# Application_-_out8_16A_-_bistable_relay_.net
KiCad netlist of a schematic drawn in EAGLE
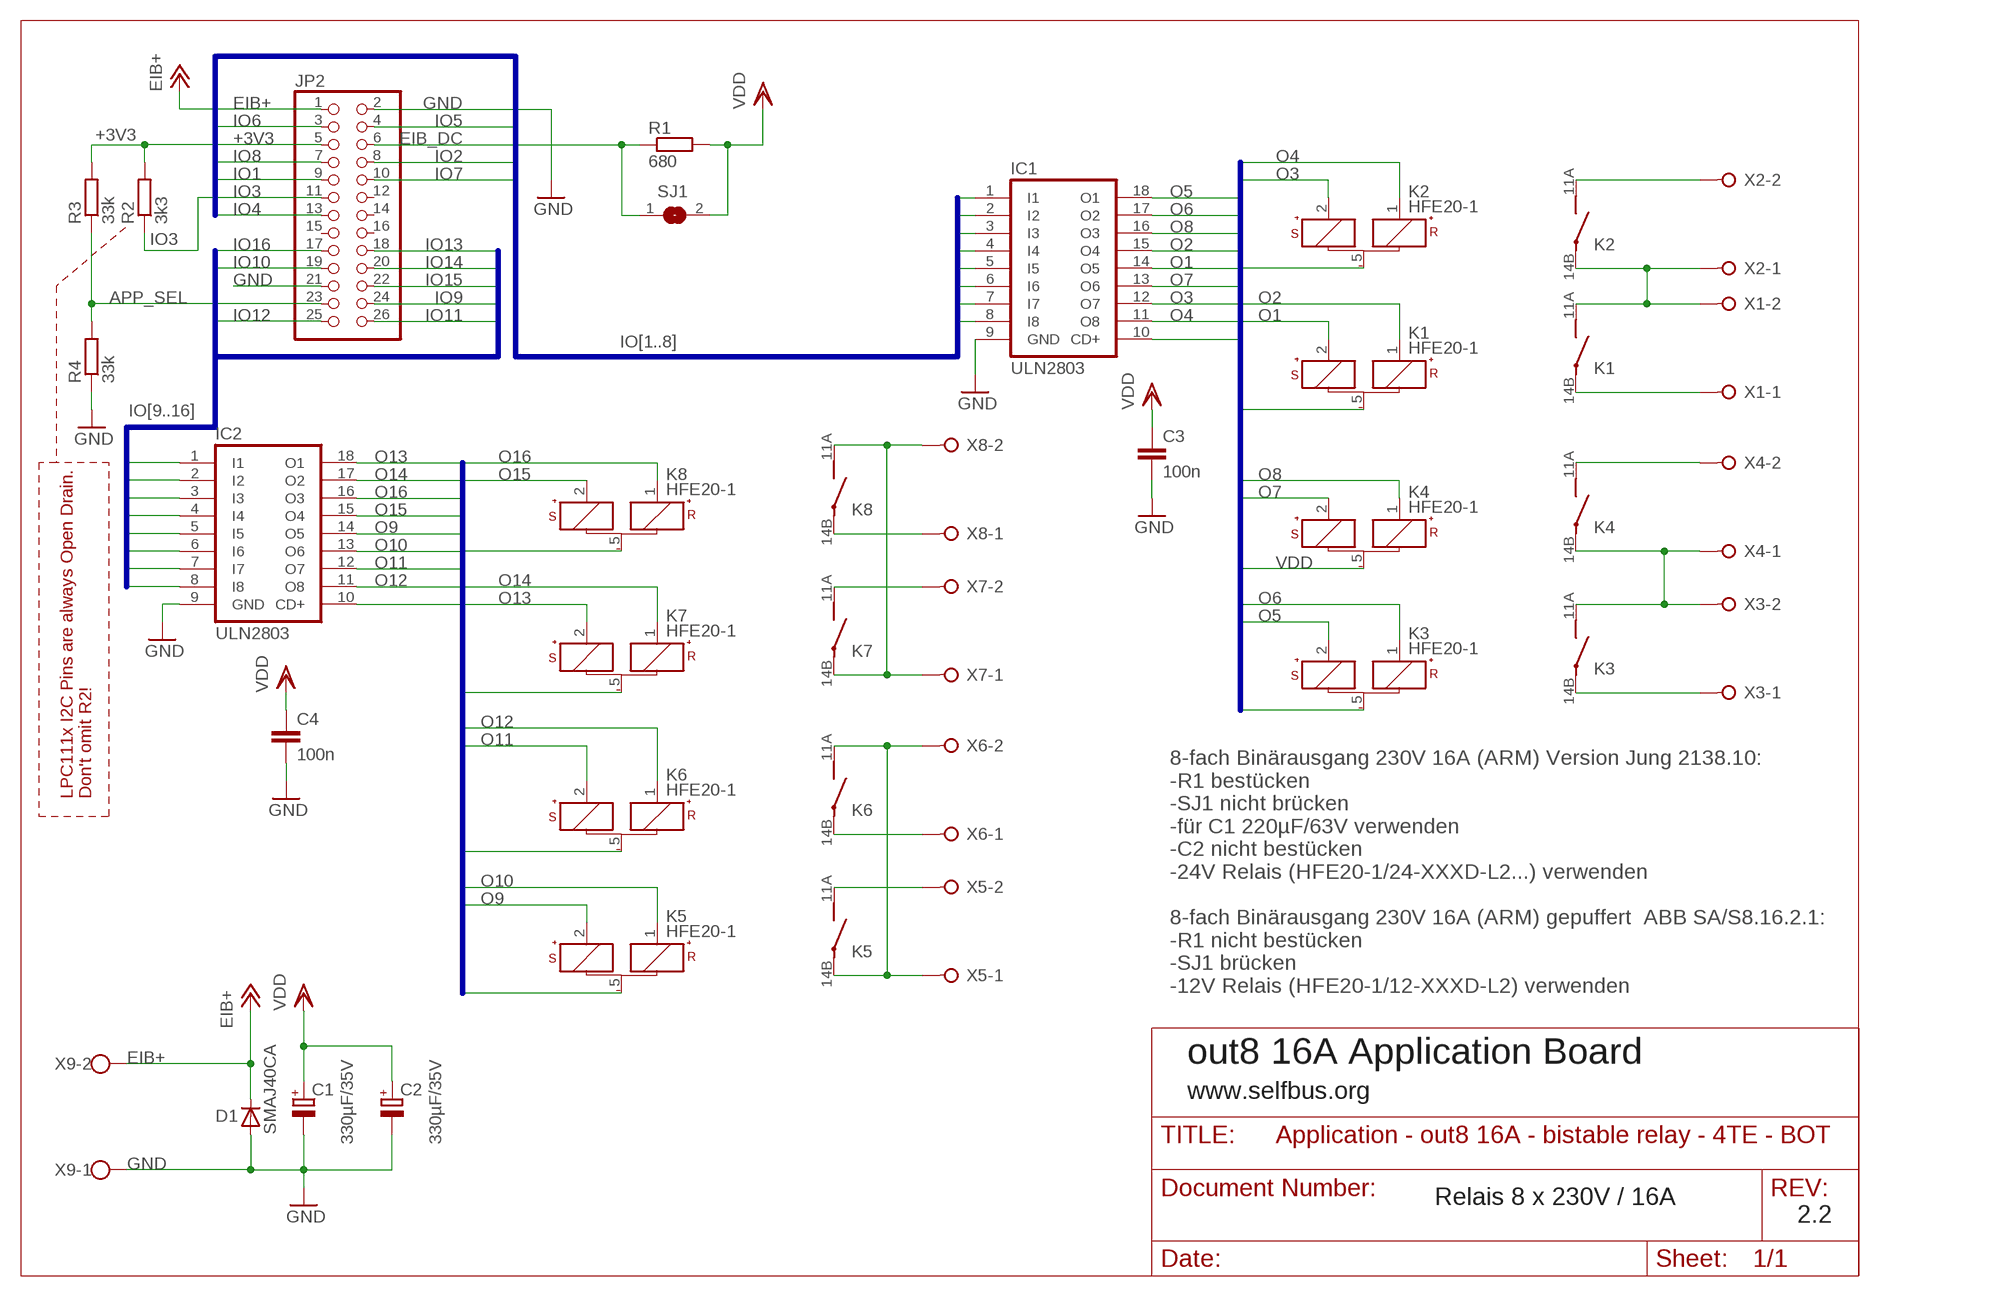
[diagram p0: schematic, sheet 1]

(export (version "E")
  (design (tool "Eeschema 10.0.6"))
  (components
    (comp (ref "C1")
      (value "330µF/35V")
      (footprint "eagle-import:E3,5-8")
      (libsource (lib "eagle-import") (part "CPOL-EUE3.5-8"))
    )
    (comp (ref "C2")
      (value "330µF/35V")
      (footprint "eagle-import:E3,5-8")
      (libsource (lib "eagle-import") (part "CPOL-EUE3.5-8"))
    )
    (comp (ref "C3")
      (value "100n")
      (footprint "eagle-import:C1206")
      (libsource (lib "eagle-import") (part "C-EUC1206"))
    )
    (comp (ref "C4")
      (value "100n")
      (footprint "eagle-import:C1206")
      (libsource (lib "eagle-import") (part "C-EUC1206"))
    )
    (comp (ref "D1")
      (value "SMAJ40CA")
      (footprint "eagle-import:SMB")
      (libsource (lib "eagle-import") (part "D-SMB"))
    )
    (comp (ref "IC1")
      (value "ULN2803")
      (footprint "eagle-import:SO18W")
      (libsource (lib "eagle-import") (part "ULN2803ASOP18"))
    )
    (comp (ref "IC2")
      (value "ULN2803")
      (footprint "eagle-import:SO18W")
      (libsource (lib "eagle-import") (part "ULN2803ASOP18"))
    )
    (comp (ref "JP2")
      (value "PINHD-2X13_2.54-SMD")
      (footprint "eagle-import:2X13SMD")
      (libsource (lib "eagle-import") (part "PINHD-2X13_2.54-SMD"))
    )
    (comp (ref "K1")
      (value "HFE20-1")
      (footprint "eagle-import:HFE20-3-504")
      (libsource (lib "eagle-import") (part "HFE20-1-024-1HD504"))
    )
    (comp (ref "K2")
      (value "HFE20-1")
      (footprint "eagle-import:HFE20-3-504")
      (libsource (lib "eagle-import") (part "HFE20-1-024-1HD504"))
    )
    (comp (ref "K3")
      (value "HFE20-1")
      (footprint "eagle-import:HFE20-3-504")
      (libsource (lib "eagle-import") (part "HFE20-1-024-1HD504"))
    )
    (comp (ref "K4")
      (value "HFE20-1")
      (footprint "eagle-import:HFE20-3-504")
      (libsource (lib "eagle-import") (part "HFE20-1-024-1HD504"))
    )
    (comp (ref "K5")
      (value "HFE20-1")
      (footprint "eagle-import:HFE20-3-504")
      (libsource (lib "eagle-import") (part "HFE20-1-024-1HD504"))
    )
    (comp (ref "K6")
      (value "HFE20-1")
      (footprint "eagle-import:HFE20-3-504")
      (libsource (lib "eagle-import") (part "HFE20-1-024-1HD504"))
    )
    (comp (ref "K7")
      (value "HFE20-1")
      (footprint "eagle-import:HFE20-3-504")
      (libsource (lib "eagle-import") (part "HFE20-1-024-1HD504"))
    )
    (comp (ref "K8")
      (value "HFE20-1")
      (footprint "eagle-import:HFE20-3-504")
      (libsource (lib "eagle-import") (part "HFE20-1-024-1HD504"))
    )
    (comp (ref "R1")
      (value "680")
      (footprint "eagle-import:M1206")
      (libsource (lib "eagle-import") (part "R-EU_M1206"))
    )
    (comp (ref "R2")
      (value "3k3")
      (footprint "eagle-import:M1206")
      (libsource (lib "eagle-import") (part "R-EU_M1206"))
    )
    (comp (ref "R3")
      (value "33k")
      (footprint "eagle-import:M1206")
      (libsource (lib "eagle-import") (part "R-EU_M1206"))
    )
    (comp (ref "R4")
      (value "33k")
      (footprint "eagle-import:M1206")
      (libsource (lib "eagle-import") (part "R-EU_M1206"))
    )
    (comp (ref "SJ1") (value "SJ") (footprint "eagle-import:SJ") (libsource (lib "eagle-import") (part "SJ")))
    (comp (ref "X1")
      (value "W237-02P")
      (footprint "eagle-import:W237-132")
      (libsource (lib "eagle-import") (part "W237-02P"))
    )
    (comp (ref "X2")
      (value "W237-02P")
      (footprint "eagle-import:W237-132")
      (libsource (lib "eagle-import") (part "W237-02P"))
    )
    (comp (ref "X3")
      (value "W237-02P")
      (footprint "eagle-import:W237-132")
      (libsource (lib "eagle-import") (part "W237-02P"))
    )
    (comp (ref "X4")
      (value "W237-02P")
      (footprint "eagle-import:W237-132")
      (libsource (lib "eagle-import") (part "W237-02P"))
    )
    (comp (ref "X5")
      (value "W237-02P")
      (footprint "eagle-import:W237-132")
      (libsource (lib "eagle-import") (part "W237-02P"))
    )
    (comp (ref "X6")
      (value "W237-02P")
      (footprint "eagle-import:W237-132")
      (libsource (lib "eagle-import") (part "W237-02P"))
    )
    (comp (ref "X7")
      (value "W237-02P")
      (footprint "eagle-import:W237-132")
      (libsource (lib "eagle-import") (part "W237-02P"))
    )
    (comp (ref "X8")
      (value "W237-02P")
      (footprint "eagle-import:W237-132")
      (libsource (lib "eagle-import") (part "W237-02P"))
    )
    (comp (ref "X9")
      (value "W237-102")
      (footprint "eagle-import:W237-102")
      (libsource (lib "eagle-import") (part "W237-102"))
    )
  )
  (nets
    (net (code "1") (name "/+3V3") (class "Default")
      (node (ref "JP2") (pin "5") (pinfunction "5_5") (pintype "passive"))
      (node (ref "R2") (pin "2") (pinfunction "2_2") (pintype "passive"))
      (node (ref "R3") (pin "2") (pinfunction "2_2") (pintype "passive"))
    )
    (net (code "2") (name "/APP_SEL") (class "Default")
      (node (ref "JP2") (pin "23") (pinfunction "23_23") (pintype "passive"))
      (node (ref "R3") (pin "1") (pinfunction "1_1") (pintype "passive"))
      (node (ref "R4") (pin "2") (pinfunction "2_2") (pintype "passive"))
    )
    (net (code "3") (name "/EIB_DC") (class "Default")
      (node (ref "JP2") (pin "6") (pinfunction "6_6") (pintype "passive"))
      (node (ref "R1") (pin "1") (pinfunction "1_1") (pintype "passive"))
      (node (ref "SJ1") (pin "1") (pinfunction "1_1") (pintype "passive"))
    )
    (net (code "4") (name "/IO1") (class "Default")
      (node (ref "IC1") (pin "5") (pinfunction "I5_5") (pintype "input"))
      (node (ref "JP2") (pin "9") (pinfunction "9_9") (pintype "passive"))
    )
    (net (code "5") (name "/IO2") (class "Default")
      (node (ref "IC1") (pin "4") (pinfunction "I4_4") (pintype "input"))
      (node (ref "JP2") (pin "8") (pinfunction "8_8") (pintype "passive"))
    )
    (net (code "6") (name "/IO3") (class "Default")
      (node (ref "IC1") (pin "7") (pinfunction "I7_7") (pintype "input"))
      (node (ref "JP2") (pin "11") (pinfunction "11_11") (pintype "passive"))
      (node (ref "R2") (pin "1") (pinfunction "1_1") (pintype "passive"))
    )
    (net (code "7") (name "/IO4") (class "Default")
      (node (ref "IC1") (pin "8") (pinfunction "I8_8") (pintype "input"))
      (node (ref "JP2") (pin "13") (pinfunction "13_13") (pintype "passive"))
    )
    (net (code "8") (name "/IO5") (class "Default")
      (node (ref "IC1") (pin "1") (pinfunction "I1_1") (pintype "input"))
      (node (ref "JP2") (pin "4") (pinfunction "4_4") (pintype "passive"))
    )
    (net (code "9") (name "/IO6") (class "Default")
      (node (ref "IC1") (pin "2") (pinfunction "I2_2") (pintype "input"))
      (node (ref "JP2") (pin "3") (pinfunction "3_3") (pintype "passive"))
    )
    (net (code "10") (name "/IO7") (class "Default")
      (node (ref "IC1") (pin "6") (pinfunction "I6_6") (pintype "input"))
      (node (ref "JP2") (pin "10") (pinfunction "10_10") (pintype "passive"))
    )
    (net (code "11") (name "/IO8") (class "Default")
      (node (ref "IC1") (pin "3") (pinfunction "I3_3") (pintype "input"))
      (node (ref "JP2") (pin "7") (pinfunction "7_7") (pintype "passive"))
    )
    (net (code "12") (name "/IO9") (class "Default")
      (node (ref "IC2") (pin "5") (pinfunction "I5_5") (pintype "input"))
      (node (ref "JP2") (pin "24") (pinfunction "24_24") (pintype "passive"))
    )
    (net (code "13") (name "/IO10") (class "Default")
      (node (ref "IC2") (pin "6") (pinfunction "I6_6") (pintype "input"))
      (node (ref "JP2") (pin "19") (pinfunction "19_19") (pintype "passive"))
    )
    (net (code "14") (name "/IO11") (class "Default")
      (node (ref "IC2") (pin "7") (pinfunction "I7_7") (pintype "input"))
      (node (ref "JP2") (pin "26") (pinfunction "26_26") (pintype "passive"))
    )
    (net (code "15") (name "/IO12") (class "Default")
      (node (ref "IC2") (pin "8") (pinfunction "I8_8") (pintype "input"))
      (node (ref "JP2") (pin "25") (pinfunction "25_25") (pintype "passive"))
    )
    (net (code "16") (name "/IO13") (class "Default")
      (node (ref "IC2") (pin "1") (pinfunction "I1_1") (pintype "input"))
      (node (ref "JP2") (pin "18") (pinfunction "18_18") (pintype "passive"))
    )
    (net (code "17") (name "/IO14") (class "Default")
      (node (ref "IC2") (pin "2") (pinfunction "I2_2") (pintype "input"))
      (node (ref "JP2") (pin "20") (pinfunction "20_20") (pintype "passive"))
    )
    (net (code "18") (name "/IO15") (class "Default")
      (node (ref "IC2") (pin "4") (pinfunction "I4_4") (pintype "input"))
      (node (ref "JP2") (pin "22") (pinfunction "22_22") (pintype "passive"))
    )
    (net (code "19") (name "/IO16") (class "Default")
      (node (ref "IC2") (pin "3") (pinfunction "I3_3") (pintype "input"))
      (node (ref "JP2") (pin "17") (pinfunction "17_17") (pintype "passive"))
    )
    (net (code "22") (name "/O1") (class "Default")
      (node (ref "IC1") (pin "14") (pinfunction "O5_14") (pintype "open_collector"))
      (node (ref "K1") (pin "2") (pinfunction "S+_2") (pintype "passive"))
    )
    (net (code "23") (name "/O2") (class "Default")
      (node (ref "IC1") (pin "15") (pinfunction "O4_15") (pintype "open_collector"))
      (node (ref "K1") (pin "1") (pinfunction "R+_1") (pintype "passive"))
    )
    (net (code "24") (name "/O3") (class "Default")
      (node (ref "IC1") (pin "12") (pinfunction "O7_12") (pintype "open_collector"))
      (node (ref "K2") (pin "2") (pinfunction "S+_2") (pintype "passive"))
    )
    (net (code "25") (name "/O4") (class "Default")
      (node (ref "IC1") (pin "11") (pinfunction "O8_11") (pintype "open_collector"))
      (node (ref "K2") (pin "1") (pinfunction "R+_1") (pintype "passive"))
    )
    (net (code "26") (name "/O5") (class "Default")
      (node (ref "IC1") (pin "18") (pinfunction "O1_18") (pintype "open_collector"))
      (node (ref "K3") (pin "2") (pinfunction "S+_2") (pintype "passive"))
    )
    (net (code "27") (name "/O6") (class "Default")
      (node (ref "IC1") (pin "17") (pinfunction "O2_17") (pintype "open_collector"))
      (node (ref "K3") (pin "1") (pinfunction "R+_1") (pintype "passive"))
    )
    (net (code "28") (name "/O7") (class "Default")
      (node (ref "IC1") (pin "13") (pinfunction "O6_13") (pintype "open_collector"))
      (node (ref "K4") (pin "2") (pinfunction "S+_2") (pintype "passive"))
    )
    (net (code "29") (name "/O8") (class "Default")
      (node (ref "IC1") (pin "16") (pinfunction "O3_16") (pintype "open_collector"))
      (node (ref "K4") (pin "1") (pinfunction "R+_1") (pintype "passive"))
    )
    (net (code "30") (name "/O9") (class "Default")
      (node (ref "IC2") (pin "14") (pinfunction "O5_14") (pintype "open_collector"))
      (node (ref "K5") (pin "2") (pinfunction "S+_2") (pintype "passive"))
    )
    (net (code "31") (name "/O10") (class "Default")
      (node (ref "IC2") (pin "13") (pinfunction "O6_13") (pintype "open_collector"))
      (node (ref "K5") (pin "1") (pinfunction "R+_1") (pintype "passive"))
    )
    (net (code "32") (name "/O11") (class "Default")
      (node (ref "IC2") (pin "12") (pinfunction "O7_12") (pintype "open_collector"))
      (node (ref "K6") (pin "2") (pinfunction "S+_2") (pintype "passive"))
    )
    (net (code "33") (name "/O12") (class "Default")
      (node (ref "IC2") (pin "11") (pinfunction "O8_11") (pintype "open_collector"))
      (node (ref "K6") (pin "1") (pinfunction "R+_1") (pintype "passive"))
    )
    (net (code "34") (name "/O13") (class "Default")
      (node (ref "IC2") (pin "18") (pinfunction "O1_18") (pintype "open_collector"))
      (node (ref "K7") (pin "2") (pinfunction "S+_2") (pintype "passive"))
    )
    (net (code "35") (name "/O14") (class "Default")
      (node (ref "IC2") (pin "17") (pinfunction "O2_17") (pintype "open_collector"))
      (node (ref "K7") (pin "1") (pinfunction "R+_1") (pintype "passive"))
    )
    (net (code "36") (name "/O15") (class "Default")
      (node (ref "IC2") (pin "15") (pinfunction "O4_15") (pintype "open_collector"))
      (node (ref "K8") (pin "2") (pinfunction "S+_2") (pintype "passive"))
    )
    (net (code "37") (name "/O16") (class "Default")
      (node (ref "IC2") (pin "16") (pinfunction "O3_16") (pintype "open_collector"))
      (node (ref "K8") (pin "1") (pinfunction "R+_1") (pintype "passive"))
    )
    (net (code "38") (name "EIB+") (class "Default")
      (node (ref "D1") (pin "1") (pinfunction "C_1") (pintype "passive"))
      (node (ref "JP2") (pin "1") (pinfunction "1_1") (pintype "passive"))
      (node (ref "X9") (pin "2") (pinfunction "KL_2") (pintype "passive"))
    )
    (net (code "39") (name "GND") (class "Default")
      (node (ref "C1") (pin "-") (pinfunction "-_-") (pintype "passive"))
      (node (ref "C2") (pin "-") (pinfunction "-_-") (pintype "passive"))
      (node (ref "C3") (pin "2") (pinfunction "2_2") (pintype "passive"))
      (node (ref "C4") (pin "2") (pinfunction "2_2") (pintype "passive"))
      (node (ref "D1") (pin "2") (pinfunction "A_2") (pintype "passive"))
      (node (ref "IC1") (pin "9") (pinfunction "GND_9") (pintype "power_in"))
      (node (ref "IC2") (pin "9") (pinfunction "GND_9") (pintype "power_in"))
      (node (ref "JP2") (pin "2") (pinfunction "2_2") (pintype "passive"))
      (node (ref "JP2") (pin "21") (pinfunction "21_21") (pintype "passive"))
      (node (ref "R4") (pin "1") (pinfunction "1_1") (pintype "passive"))
      (node (ref "X9") (pin "1") (pinfunction "KL_1") (pintype "passive"))
    )
    (net (code "40") (name "Net-(K1B-PA)") (class "Default")
      (node (ref "K1") (pin "14B") (pinfunction "PA_14B") (pintype "passive"))
      (node (ref "X1") (pin "1") (pinfunction "KL_1") (pintype "passive"))
    )
    (net (code "41") (name "Net-(K1B-PB)") (class "Default")
      (node (ref "K1") (pin "11A") (pinfunction "PB_11A") (pintype "passive"))
      (node (ref "K2") (pin "14B") (pinfunction "PA_14B") (pintype "passive"))
      (node (ref "X1") (pin "2") (pinfunction "KL_2") (pintype "passive"))
      (node (ref "X2") (pin "1") (pinfunction "KL_1") (pintype "passive"))
    )
    (net (code "42") (name "Net-(K2B-PB)") (class "Default")
      (node (ref "K2") (pin "11A") (pinfunction "PB_11A") (pintype "passive"))
      (node (ref "X2") (pin "2") (pinfunction "KL_2") (pintype "passive"))
    )
    (net (code "43") (name "Net-(K3B-PA)") (class "Default")
      (node (ref "K3") (pin "14B") (pinfunction "PA_14B") (pintype "passive"))
      (node (ref "X3") (pin "1") (pinfunction "KL_1") (pintype "passive"))
    )
    (net (code "44") (name "Net-(K3B-PB)") (class "Default")
      (node (ref "K3") (pin "11A") (pinfunction "PB_11A") (pintype "passive"))
      (node (ref "K4") (pin "14B") (pinfunction "PA_14B") (pintype "passive"))
      (node (ref "X3") (pin "2") (pinfunction "KL_2") (pintype "passive"))
      (node (ref "X4") (pin "1") (pinfunction "KL_1") (pintype "passive"))
    )
    (net (code "45") (name "Net-(K4B-PB)") (class "Default")
      (node (ref "K4") (pin "11A") (pinfunction "PB_11A") (pintype "passive"))
      (node (ref "X4") (pin "2") (pinfunction "KL_2") (pintype "passive"))
    )
    (net (code "46") (name "Net-(K5B-PA)") (class "Default")
      (node (ref "K5") (pin "14B") (pinfunction "PA_14B") (pintype "passive"))
      (node (ref "K6") (pin "11A") (pinfunction "PB_11A") (pintype "passive"))
      (node (ref "X5") (pin "1") (pinfunction "KL_1") (pintype "passive"))
      (node (ref "X6") (pin "2") (pinfunction "KL_2") (pintype "passive"))
    )
    (net (code "47") (name "Net-(K5B-PB)") (class "Default")
      (node (ref "K5") (pin "11A") (pinfunction "PB_11A") (pintype "passive"))
      (node (ref "X5") (pin "2") (pinfunction "KL_2") (pintype "passive"))
    )
    (net (code "48") (name "Net-(K6B-PA)") (class "Default")
      (node (ref "K6") (pin "14B") (pinfunction "PA_14B") (pintype "passive"))
      (node (ref "X6") (pin "1") (pinfunction "KL_1") (pintype "passive"))
    )
    (net (code "49") (name "Net-(K7B-PA)") (class "Default")
      (node (ref "K7") (pin "14B") (pinfunction "PA_14B") (pintype "passive"))
      (node (ref "K8") (pin "11A") (pinfunction "PB_11A") (pintype "passive"))
      (node (ref "X7") (pin "1") (pinfunction "KL_1") (pintype "passive"))
      (node (ref "X8") (pin "2") (pinfunction "KL_2") (pintype "passive"))
    )
    (net (code "50") (name "Net-(K7B-PB)") (class "Default")
      (node (ref "K7") (pin "11A") (pinfunction "PB_11A") (pintype "passive"))
      (node (ref "X7") (pin "2") (pinfunction "KL_2") (pintype "passive"))
    )
    (net (code "51") (name "Net-(K8B-PA)") (class "Default")
      (node (ref "K8") (pin "14B") (pinfunction "PA_14B") (pintype "passive"))
      (node (ref "X8") (pin "1") (pinfunction "KL_1") (pintype "passive"))
    )
    (net (code "52") (name "VDD") (class "Default")
      (node (ref "C1") (pin "+") (pinfunction "+_+") (pintype "passive"))
      (node (ref "C2") (pin "+") (pinfunction "+_+") (pintype "passive"))
      (node (ref "C3") (pin "1") (pinfunction "1_1") (pintype "passive"))
      (node (ref "C4") (pin "1") (pinfunction "1_1") (pintype "passive"))
      (node (ref "IC1") (pin "10") (pinfunction "CD+_10") (pintype "passive"))
      (node (ref "IC2") (pin "10") (pinfunction "CD+_10") (pintype "passive"))
      (node (ref "K1") (pin "5") (pinfunction "-_5") (pintype "passive"))
      (node (ref "K2") (pin "5") (pinfunction "-_5") (pintype "passive"))
      (node (ref "K3") (pin "5") (pinfunction "-_5") (pintype "passive"))
      (node (ref "K4") (pin "5") (pinfunction "-_5") (pintype "passive"))
      (node (ref "K5") (pin "5") (pinfunction "-_5") (pintype "passive"))
      (node (ref "K6") (pin "5") (pinfunction "-_5") (pintype "passive"))
      (node (ref "K7") (pin "5") (pinfunction "-_5") (pintype "passive"))
      (node (ref "K8") (pin "5") (pinfunction "-_5") (pintype "passive"))
      (node (ref "R1") (pin "2") (pinfunction "2_2") (pintype "passive"))
      (node (ref "SJ1") (pin "2") (pinfunction "2_2") (pintype "passive"))
    )
    (net (code "53") (name "unconnected-(JP2-Pad12)") (class "Default")
      (node (ref "JP2") (pin "12") (pinfunction "12_12") (pintype "passive"))
    )
    (net (code "54") (name "unconnected-(JP2-Pad14)") (class "Default")
      (node (ref "JP2") (pin "14") (pinfunction "14_14") (pintype "passive"))
    )
    (net (code "55") (name "unconnected-(JP2-Pad15)") (class "Default")
      (node (ref "JP2") (pin "15") (pinfunction "15_15") (pintype "passive"))
    )
    (net (code "56") (name "unconnected-(JP2-Pad16)") (class "Default")
      (node (ref "JP2") (pin "16") (pinfunction "16_16") (pintype "passive"))
    )
  )
)
